# sanfrancisco_barometer_rev_C.net
KiCad netlist of a schematic drawn in EAGLE
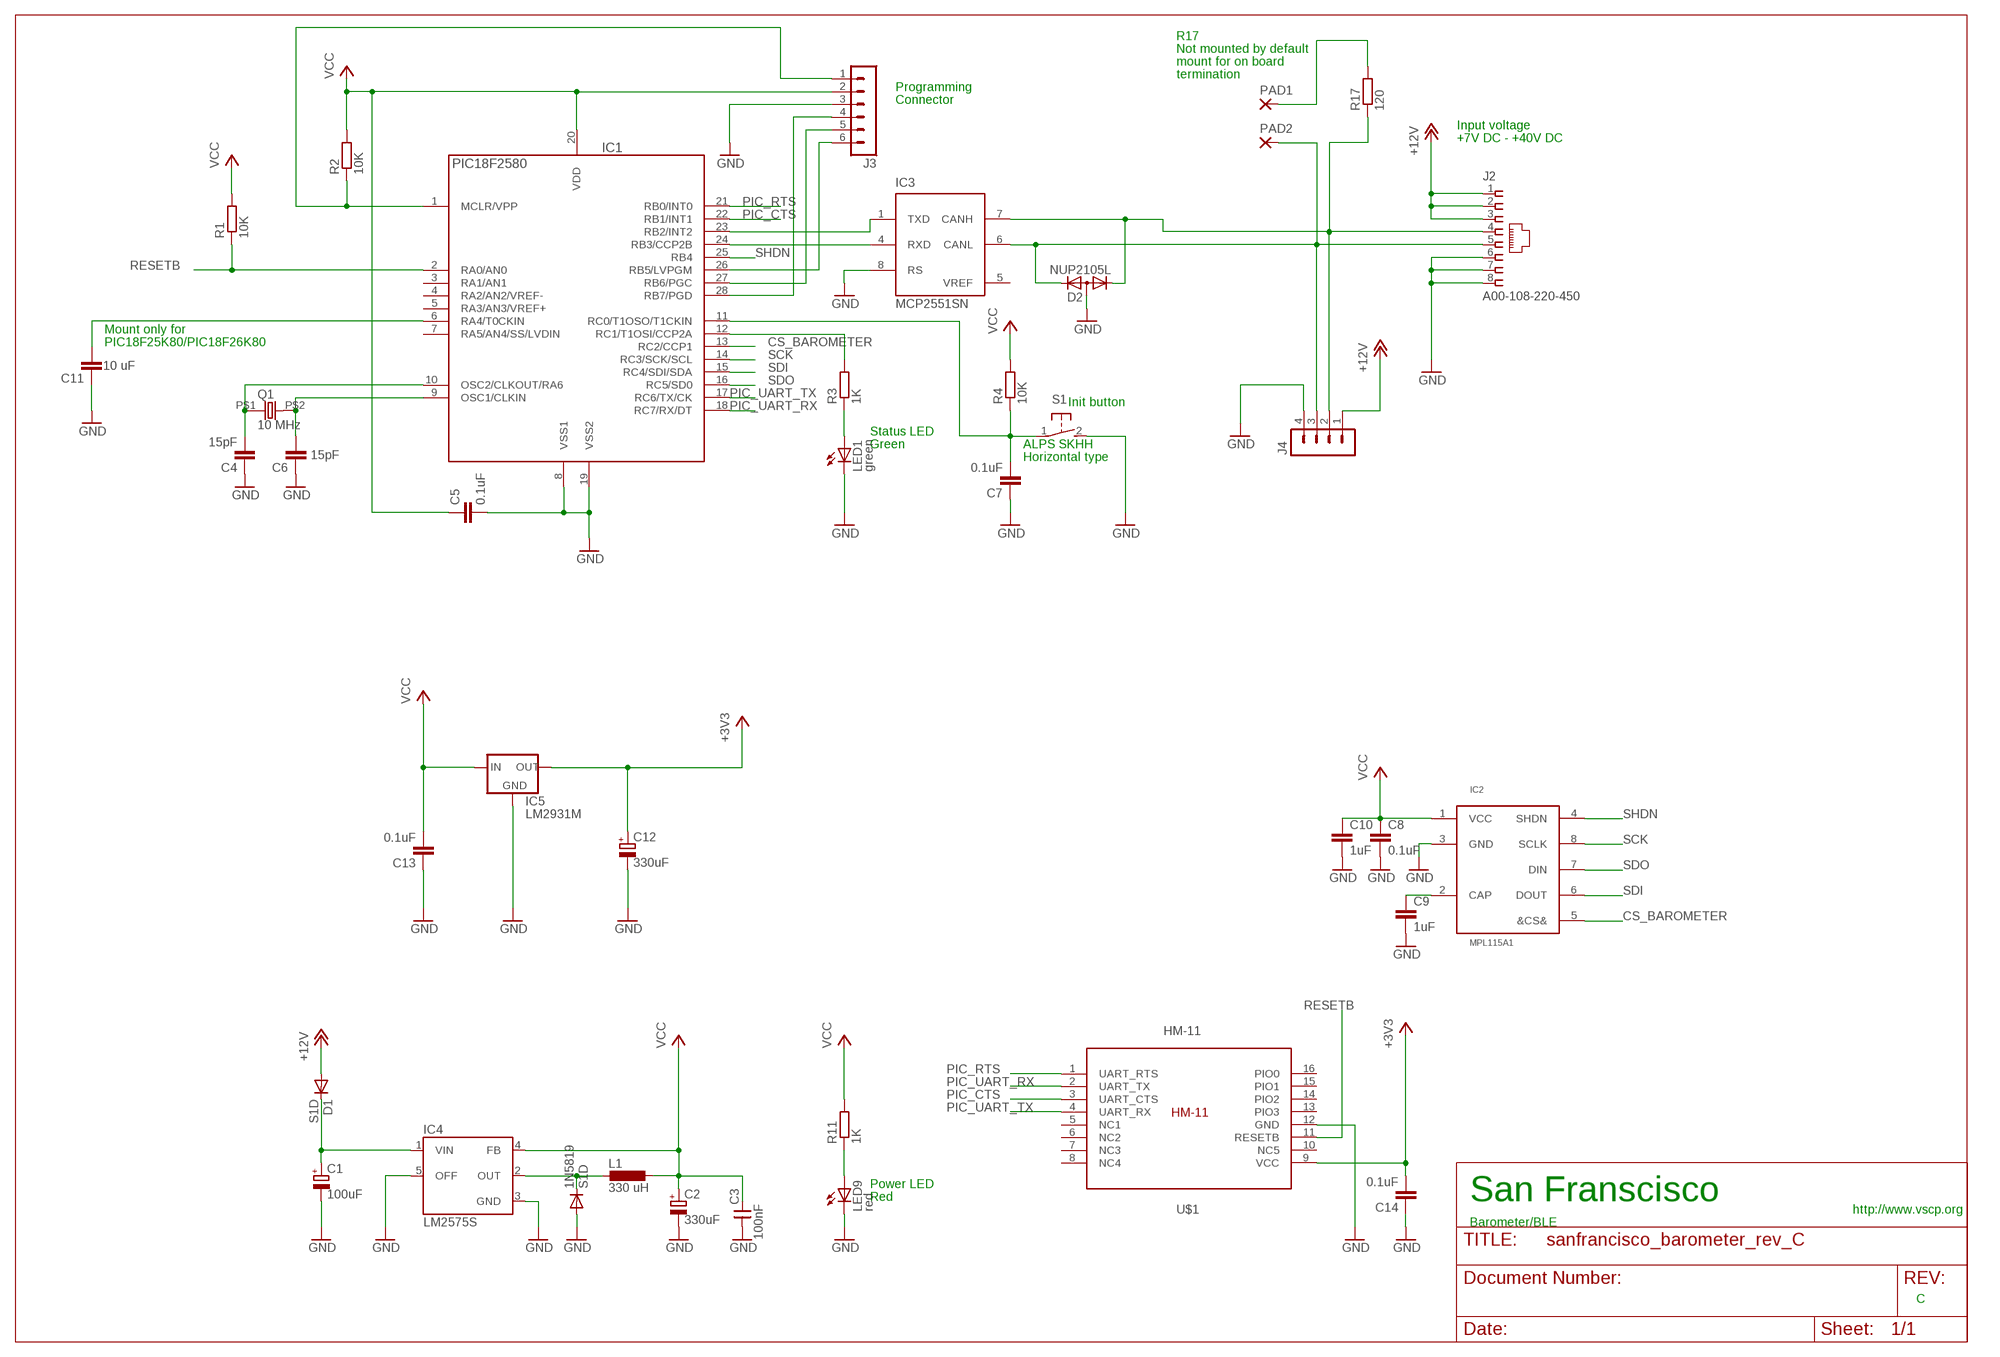
[diagram p0: schematic, sheet 1]

(export (version "E")
  (design (tool "Eeschema 10.0.6"))
  (components
    (comp (ref "1N5819")
      (value "S1D")
      (footprint "eagle-import:SOD123")
      (libsource (lib "eagle-import") (part "DIODE-SOD123"))
    )
    (comp (ref "C1")
      (value "100uF")
      (footprint "eagle-import:PANASONIC_D")
      (libsource (lib "eagle-import") (part "CPOL-EUD"))
    )
    (comp (ref "C2")
      (value "330uF")
      (footprint "eagle-import:PANASONIC_D")
      (libsource (lib "eagle-import") (part "CPOL-EUD"))
    )
    (comp (ref "C3")
      (value "100nF")
      (footprint "eagle-import:0805")
      (libsource (lib "eagle-import") (part "CNP-0805"))
    )
    (comp (ref "C4")
      (value "15pF")
      (footprint "eagle-import:C0805")
      (libsource (lib "eagle-import") (part "C-EUC0805"))
    )
    (comp (ref "C5")
      (value "0.1uF")
      (footprint "eagle-import:C0805")
      (libsource (lib "eagle-import") (part "C-EUC0805"))
    )
    (comp (ref "C6")
      (value "15pF")
      (footprint "eagle-import:C0805")
      (libsource (lib "eagle-import") (part "C-EUC0805"))
    )
    (comp (ref "C7")
      (value "0.1uF")
      (footprint "eagle-import:C0805")
      (libsource (lib "eagle-import") (part "C-EUC0805"))
    )
    (comp (ref "C8")
      (value "0.1uF")
      (footprint "eagle-import:C0805")
      (libsource (lib "eagle-import") (part "C-EUC0805"))
    )
    (comp (ref "C9")
      (value "1uF")
      (footprint "eagle-import:C0805")
      (libsource (lib "eagle-import") (part "C-EUC0805"))
    )
    (comp (ref "C10")
      (value "1uF")
      (footprint "eagle-import:C0805")
      (libsource (lib "eagle-import") (part "C-EUC0805"))
    )
    (comp (ref "C11")
      (value "10 uF")
      (footprint "eagle-import:C0805")
      (libsource (lib "eagle-import") (part "C-EUC0805"))
    )
    (comp (ref "C12")
      (value "330uF")
      (footprint "eagle-import:PANASONIC_D")
      (libsource (lib "eagle-import") (part "CPOL-EUD"))
    )
    (comp (ref "C13")
      (value "0.1uF")
      (footprint "eagle-import:C0805")
      (libsource (lib "eagle-import") (part "C-EUC0805"))
    )
    (comp (ref "C14")
      (value "0.1uF")
      (footprint "eagle-import:C0805")
      (libsource (lib "eagle-import") (part "C-EUC0805"))
    )
    (comp (ref "D1")
      (value "S1D")
      (footprint "eagle-import:SOD123")
      (libsource (lib "eagle-import") (part "DIODE-SOD123"))
    )
    (comp (ref "D2")
      (value "NUP2105L")
      (footprint "eagle-import:SOT23")
      (libsource (lib "eagle-import") (part "DIODE-2CA|ACSOT23"))
    )
    (comp (ref "IC1")
      (value "PIC18F2580")
      (footprint "eagle-import:SO28")
      (libsource (lib "eagle-import") (part "PIC18F252-?I/SOL"))
    )
    (comp (ref "IC2")
      (value "MPL115A1")
      (footprint "eagle-import:LGA8")
      (libsource (lib "eagle-import") (part "MPL115A1"))
    )
    (comp (ref "IC3")
      (value "MCP2551SN")
      (footprint "eagle-import:SO-08")
      (libsource (lib "eagle-import") (part "MCP2551SN"))
    )
    (comp (ref "IC4")
      (value "LM2575S")
      (footprint "eagle-import:TO263-5")
      (libsource (lib "eagle-import") (part "LM2575S"))
    )
    (comp (ref "IC5")
      (value "LM2931M")
      (footprint "eagle-import:SO08")
      (libsource (lib "eagle-import") (part "LM2931M"))
    )
    (comp (ref "J2")
      (value "A00-108-220-450")
      (footprint "eagle-import:RJ-45")
      (libsource (lib "eagle-import") (part "A00-108-220-450"))
    )
    (comp (ref "J3")
      (value "MA06-1")
      (footprint "eagle-import:MA06-1")
      (libsource (lib "eagle-import") (part "MA06-1"))
    )
    (comp (ref "J4")
      (value "MA04-1")
      (footprint "eagle-import:MA04-1")
      (libsource (lib "eagle-import") (part "MA04-1"))
    )
    (comp (ref "L1")
      (value "330 uH")
      (footprint "eagle-import:DO3316P")
      (libsource (lib "eagle-import") (part "DO3316P"))
    )
    (comp (ref "LED1")
      (value "green")
      (footprint "eagle-import:CHIP-LED0805")
      (libsource (lib "eagle-import") (part "LEDCHIP-LED0805"))
    )
    (comp (ref "LED9")
      (value "red")
      (footprint "eagle-import:CHIP-LED0805")
      (libsource (lib "eagle-import") (part "LEDCHIP-LED0805"))
    )
    (comp (ref "PAD1")
      (value "1,6/0,8")
      (footprint "eagle-import:1,6_0,8")
      (libsource (lib "eagle-import") (part "1,6/0,8"))
    )
    (comp (ref "PAD2")
      (value "1,6/0,8")
      (footprint "eagle-import:1,6_0,8")
      (libsource (lib "eagle-import") (part "1,6/0,8"))
    )
    (comp (ref "Q1")
      (value "10 MHz")
      (footprint "eagle-import:9C")
      (libsource (lib "eagle-import") (part "HC-49S"))
    )
    (comp (ref "R1")
      (value "10K")
      (footprint "eagle-import:R0805")
      (libsource (lib "eagle-import") (part "R-EU_R0805"))
    )
    (comp (ref "R2")
      (value "10K")
      (footprint "eagle-import:R0805")
      (libsource (lib "eagle-import") (part "R-EU_R0805"))
    )
    (comp (ref "R3")
      (value "1K")
      (footprint "eagle-import:R0805")
      (libsource (lib "eagle-import") (part "R-EU_R0805"))
    )
    (comp (ref "R4")
      (value "10K")
      (footprint "eagle-import:R0805")
      (libsource (lib "eagle-import") (part "R-EU_R0805"))
    )
    (comp (ref "R11")
      (value "1K")
      (footprint "eagle-import:R0805")
      (libsource (lib "eagle-import") (part "R-EU_R0805"))
    )
    (comp (ref "R17")
      (value "120")
      (footprint "eagle-import:R0805")
      (libsource (lib "eagle-import") (part "R-EU_R0805"))
    )
    (comp (ref "S1")
      (value "31-XX")
      (footprint "eagle-import:B3F-31XX")
      (fields (field (name "MPN") "B3F-3100"))
      (libsource (lib "eagle-import") (part "31-XX"))
    )
    (comp (ref "U$1")
      (value "HM-11")
      (footprint "eagle-import:HM-11")
      (libsource (lib "eagle-import") (part "HM-11"))
    )
  )
  (nets
    (net (code "1") (name "+3V3") (class "Default")
      (node (ref "C12") (pin "+") (pinfunction "+_+") (pintype "passive"))
      (node (ref "C14") (pin "2") (pinfunction "2_2") (pintype "passive"))
      (node (ref "IC5") (pin "1") (pinfunction "OUT_1") (pintype "passive"))
      (node (ref "U$1") (pin "9") (pinfunction "VCC_9") (pintype "power_in"))
    )
    (net (code "2") (name "+12V") (class "Default")
      (node (ref "D1") (pin "A") (pinfunction "A_A") (pintype "passive"))
      (node (ref "J2") (pin "1") (pinfunction "1_1") (pintype "passive"))
      (node (ref "J2") (pin "2") (pinfunction "2_2") (pintype "passive"))
      (node (ref "J2") (pin "3") (pinfunction "3_3") (pintype "passive"))
      (node (ref "J4") (pin "1") (pinfunction "1_1") (pintype "passive"))
    )
    (net (code "3") (name "/CS_BAROMETER") (class "Default")
      (node (ref "IC1") (pin "13") (pinfunction "RC2/CCP1_13") (pintype "bidirectional"))
      (node (ref "IC2") (pin "5") (pinfunction "&CS&_5") (pintype "input"))
    )
    (net (code "4") (name "/PIC_CTS") (class "Default")
      (node (ref "IC1") (pin "22") (pinfunction "RB1/INT1_22") (pintype "bidirectional"))
      (node (ref "U$1") (pin "3") (pinfunction "UART_CTS_3") (pintype "bidirectional"))
    )
    (net (code "5") (name "/PIC_RTS") (class "Default")
      (node (ref "IC1") (pin "21") (pinfunction "RB0/INT0_21") (pintype "bidirectional"))
      (node (ref "U$1") (pin "1") (pinfunction "UART_RTS_1") (pintype "bidirectional"))
    )
    (net (code "6") (name "/PIC_UART_RX") (class "Default")
      (node (ref "IC1") (pin "18") (pinfunction "RC7/RX/DT_18") (pintype "bidirectional"))
      (node (ref "U$1") (pin "2") (pinfunction "UART_TX_2") (pintype "bidirectional"))
    )
    (net (code "7") (name "/PIC_UART_TX") (class "Default")
      (node (ref "IC1") (pin "17") (pinfunction "RC6/TX/CK_17") (pintype "bidirectional"))
      (node (ref "U$1") (pin "4") (pinfunction "UART_RX_4") (pintype "bidirectional"))
    )
    (net (code "8") (name "/RESETB") (class "Default")
      (node (ref "IC1") (pin "2") (pinfunction "RA0/AN0_2") (pintype "bidirectional"))
      (node (ref "R1") (pin "1") (pinfunction "1_1") (pintype "passive"))
      (node (ref "U$1") (pin "11") (pinfunction "RESETB_11") (pintype "bidirectional"))
    )
    (net (code "9") (name "/SCK") (class "Default")
      (node (ref "IC1") (pin "14") (pinfunction "RC3/SCK/SCL_14") (pintype "bidirectional"))
      (node (ref "IC2") (pin "8") (pinfunction "SCLK_8") (pintype "input"))
    )
    (net (code "10") (name "/SDI") (class "Default")
      (node (ref "IC1") (pin "15") (pinfunction "RC4/SDI/SDA_15") (pintype "bidirectional"))
      (node (ref "IC2") (pin "6") (pinfunction "DOUT_6") (pintype "output"))
    )
    (net (code "11") (name "/SDO") (class "Default")
      (node (ref "IC1") (pin "16") (pinfunction "RC5/SD0_16") (pintype "bidirectional"))
      (node (ref "IC2") (pin "7") (pinfunction "DIN_7") (pintype "input"))
    )
    (net (code "12") (name "/SHDN") (class "Default")
      (node (ref "IC1") (pin "25") (pinfunction "RB4_25") (pintype "bidirectional"))
      (node (ref "IC2") (pin "4") (pinfunction "SHDN_4") (pintype "input"))
    )
    (net (code "13") (name "/VREF") (class "Default")
      (node (ref "IC3") (pin "5") (pinfunction "VREF_5") (pintype "power_in"))
    )
    (net (code "14") (name "GND") (class "Default")
      (node (ref "1N5819") (pin "A") (pinfunction "A_A") (pintype "passive"))
      (node (ref "C1") (pin "-") (pinfunction "-_-") (pintype "passive"))
      (node (ref "C10") (pin "2") (pinfunction "2_2") (pintype "passive"))
      (node (ref "C11") (pin "1") (pinfunction "1_1") (pintype "passive"))
      (node (ref "C12") (pin "-") (pinfunction "-_-") (pintype "passive"))
      (node (ref "C13") (pin "1") (pinfunction "1_1") (pintype "passive"))
      (node (ref "C14") (pin "1") (pinfunction "1_1") (pintype "passive"))
      (node (ref "C2") (pin "-") (pinfunction "-_-") (pintype "passive"))
      (node (ref "C3") (pin "1") (pinfunction "1_1") (pintype "passive"))
      (node (ref "C4") (pin "1") (pinfunction "1_1") (pintype "passive"))
      (node (ref "C5") (pin "2") (pinfunction "2_2") (pintype "passive"))
      (node (ref "C6") (pin "1") (pinfunction "1_1") (pintype "passive"))
      (node (ref "C7") (pin "1") (pinfunction "1_1") (pintype "passive"))
      (node (ref "C8") (pin "2") (pinfunction "2_2") (pintype "passive"))
      (node (ref "C9") (pin "2") (pinfunction "2_2") (pintype "passive"))
      (node (ref "D2") (pin "3") (pinfunction "A_3") (pintype "passive"))
      (node (ref "IC1") (pin "19") (pinfunction "VSS2_19") (pintype "power_in"))
      (node (ref "IC1") (pin "8") (pinfunction "VSS1_8") (pintype "power_in"))
      (node (ref "IC2") (pin "3") (pinfunction "GND_3") (pintype "power_in"))
      (node (ref "IC3") (pin "8") (pinfunction "RS_8") (pintype "input"))
      (node (ref "IC4") (pin "3") (pinfunction "GND_3") (pintype "power_in"))
      (node (ref "IC4") (pin "5") (pinfunction "OFF_5") (pintype "input"))
      (node (ref "IC5") (pin "2") (pinfunction "GND_2") (pintype "input"))
      (node (ref "J2") (pin "6") (pinfunction "6_6") (pintype "passive"))
      (node (ref "J2") (pin "7") (pinfunction "7_7") (pintype "passive"))
      (node (ref "J2") (pin "8") (pinfunction "8_8") (pintype "passive"))
      (node (ref "J3") (pin "3") (pinfunction "3_3") (pintype "passive"))
      (node (ref "J4") (pin "4") (pinfunction "4_4") (pintype "passive"))
      (node (ref "LED1") (pin "C") (pinfunction "C_C") (pintype "passive"))
      (node (ref "LED9") (pin "C") (pinfunction "C_C") (pintype "passive"))
      (node (ref "S1") (pin "2") (pinfunction "S_2") (pintype "passive"))
      (node (ref "U$1") (pin "12") (pinfunction "GND_12") (pintype "power_in"))
    )
    (net (code "15") (name "Net-(D2-K1)") (class "Default")
      (node (ref "D2") (pin "1") (pinfunction "K1_1") (pintype "passive"))
      (node (ref "IC3") (pin "7") (pinfunction "CANH_7") (pintype "bidirectional"))
      (node (ref "J2") (pin "4") (pinfunction "4_4") (pintype "passive"))
      (node (ref "J4") (pin "2") (pinfunction "2_2") (pintype "passive"))
      (node (ref "R17") (pin "1") (pinfunction "1_1") (pintype "passive"))
    )
    (net (code "16") (name "Net-(D2-K2)") (class "Default")
      (node (ref "D2") (pin "2") (pinfunction "K2_2") (pintype "passive"))
      (node (ref "IC3") (pin "6") (pinfunction "CANL_6") (pintype "bidirectional"))
      (node (ref "J2") (pin "5") (pinfunction "5_5") (pintype "passive"))
      (node (ref "J4") (pin "3") (pinfunction "3_3") (pintype "passive"))
      (node (ref "PAD2") (pin "1") (pinfunction "P_1") (pintype "passive"))
    )
    (net (code "17") (name "Net-(IC1-MCLR{slash}VPP)") (class "Default")
      (node (ref "IC1") (pin "1") (pinfunction "MCLR/VPP_1") (pintype "input"))
      (node (ref "J3") (pin "1") (pinfunction "1_1") (pintype "passive"))
      (node (ref "R2") (pin "1") (pinfunction "1_1") (pintype "passive"))
    )
    (net (code "18") (name "Net-(IC1-OSC1{slash}CLKIN)") (class "Default")
      (node (ref "C6") (pin "2") (pinfunction "2_2") (pintype "passive"))
      (node (ref "IC1") (pin "9") (pinfunction "OSC1/CLKIN_9") (pintype "input"))
      (node (ref "Q1") (pin "P$2") (pinfunction "2_P$2") (pintype "passive"))
    )
    (net (code "19") (name "Net-(IC1-OSC2{slash}CLKOUT{slash}RA6)") (class "Default")
      (node (ref "C4") (pin "2") (pinfunction "2_2") (pintype "passive"))
      (node (ref "IC1") (pin "10") (pinfunction "OSC2/CLKOUT/RA6_10") (pintype "output"))
      (node (ref "Q1") (pin "P$1") (pinfunction "1_P$1") (pintype "passive"))
    )
    (net (code "20") (name "Net-(IC1-RA4{slash}T0CKIN)") (class "Default")
      (node (ref "C11") (pin "2") (pinfunction "2_2") (pintype "passive"))
      (node (ref "IC1") (pin "6") (pinfunction "RA4/T0CKIN_6") (pintype "open_collector"))
    )
    (net (code "21") (name "Net-(IC1-RB2{slash}INT2)") (class "Default")
      (node (ref "IC1") (pin "23") (pinfunction "RB2/INT2_23") (pintype "bidirectional"))
      (node (ref "IC3") (pin "1") (pinfunction "TXD_1") (pintype "input"))
    )
    (net (code "22") (name "Net-(IC1-RB3{slash}CCP2B)") (class "Default")
      (node (ref "IC1") (pin "24") (pinfunction "RB3/CCP2B_24") (pintype "bidirectional"))
      (node (ref "IC3") (pin "4") (pinfunction "RXD_4") (pintype "output"))
    )
    (net (code "23") (name "Net-(IC1-RB5{slash}LVPGM)") (class "Default")
      (node (ref "IC1") (pin "26") (pinfunction "RB5/LVPGM_26") (pintype "bidirectional"))
      (node (ref "J3") (pin "6") (pinfunction "6_6") (pintype "passive"))
    )
    (net (code "24") (name "Net-(IC1-RB6{slash}PGC)") (class "Default")
      (node (ref "IC1") (pin "27") (pinfunction "RB6/PGC_27") (pintype "bidirectional"))
      (node (ref "J3") (pin "5") (pinfunction "5_5") (pintype "passive"))
    )
    (net (code "25") (name "Net-(IC1-RB7{slash}PGD)") (class "Default")
      (node (ref "IC1") (pin "28") (pinfunction "RB7/PGD_28") (pintype "bidirectional"))
      (node (ref "J3") (pin "4") (pinfunction "4_4") (pintype "passive"))
    )
    (net (code "26") (name "Net-(IC1-RC0{slash}T1OSO{slash}T1CKIN)") (class "Default")
      (node (ref "C7") (pin "2") (pinfunction "2_2") (pintype "passive"))
      (node (ref "IC1") (pin "11") (pinfunction "RC0/T1OSO/T1CKIN_11") (pintype "bidirectional"))
      (node (ref "R4") (pin "1") (pinfunction "1_1") (pintype "passive"))
      (node (ref "S1") (pin "1") (pinfunction "P_1") (pintype "passive"))
    )
    (net (code "27") (name "Net-(IC1-RC1{slash}T1OSI{slash}CCP2A)") (class "Default")
      (node (ref "IC1") (pin "12") (pinfunction "RC1/T1OSI/CCP2A_12") (pintype "bidirectional"))
      (node (ref "R3") (pin "2") (pinfunction "2_2") (pintype "passive"))
    )
    (net (code "28") (name "Net-(IC2-CAP)") (class "Default")
      (node (ref "C9") (pin "1") (pinfunction "1_1") (pintype "passive"))
      (node (ref "IC2") (pin "2") (pinfunction "CAP_2") (pintype "power_in"))
    )
    (net (code "29") (name "Net-(IC4-OUT)") (class "Default")
      (node (ref "1N5819") (pin "C") (pinfunction "C_C") (pintype "passive"))
      (node (ref "IC4") (pin "2") (pinfunction "OUT_2") (pintype "output"))
      (node (ref "L1") (pin "1") (pinfunction "1_1") (pintype "passive"))
    )
    (net (code "30") (name "Net-(IC4-VIN)") (class "Default")
      (node (ref "C1") (pin "+") (pinfunction "+_+") (pintype "passive"))
      (node (ref "D1") (pin "C") (pinfunction "C_C") (pintype "passive"))
      (node (ref "IC4") (pin "1") (pinfunction "VIN_1") (pintype "power_in"))
    )
    (net (code "31") (name "Net-(LED1-PadA)") (class "Default")
      (node (ref "LED1") (pin "A") (pinfunction "A_A") (pintype "passive"))
      (node (ref "R3") (pin "1") (pinfunction "1_1") (pintype "passive"))
    )
    (net (code "32") (name "Net-(LED9-PadA)") (class "Default")
      (node (ref "LED9") (pin "A") (pinfunction "A_A") (pintype "passive"))
      (node (ref "R11") (pin "1") (pinfunction "1_1") (pintype "passive"))
    )
    (net (code "33") (name "Net-(PAD1-P)") (class "Default")
      (node (ref "PAD1") (pin "1") (pinfunction "P_1") (pintype "passive"))
      (node (ref "R17") (pin "2") (pinfunction "2_2") (pintype "passive"))
    )
    (net (code "34") (name "VCC") (class "Default")
      (node (ref "C10") (pin "1") (pinfunction "1_1") (pintype "passive"))
      (node (ref "C13") (pin "2") (pinfunction "2_2") (pintype "passive"))
      (node (ref "C2") (pin "+") (pinfunction "+_+") (pintype "passive"))
      (node (ref "C3") (pin "2") (pinfunction "2_2") (pintype "passive"))
      (node (ref "C5") (pin "1") (pinfunction "1_1") (pintype "passive"))
      (node (ref "C8") (pin "1") (pinfunction "1_1") (pintype "passive"))
      (node (ref "IC1") (pin "20") (pinfunction "VDD_20") (pintype "power_in"))
      (node (ref "IC2") (pin "1") (pinfunction "VCC_1") (pintype "power_in"))
      (node (ref "IC4") (pin "4") (pinfunction "FB_4") (pintype "input"))
      (node (ref "IC5") (pin "8") (pinfunction "IN_8") (pintype "input"))
      (node (ref "J3") (pin "2") (pinfunction "2_2") (pintype "passive"))
      (node (ref "L1") (pin "2") (pinfunction "2_2") (pintype "passive"))
      (node (ref "R1") (pin "2") (pinfunction "2_2") (pintype "passive"))
      (node (ref "R11") (pin "2") (pinfunction "2_2") (pintype "passive"))
      (node (ref "R2") (pin "2") (pinfunction "2_2") (pintype "passive"))
      (node (ref "R4") (pin "2") (pinfunction "2_2") (pintype "passive"))
    )
    (net (code "35") (name "unconnected-(IC1-RA1{slash}AN1-Pad3)") (class "Default")
      (node (ref "IC1") (pin "3") (pinfunction "RA1/AN1_3") (pintype "bidirectional"))
    )
    (net (code "36") (name "unconnected-(IC1-RA2{slash}AN2{slash}VREF--Pad4)") (class "Default")
      (node (ref "IC1") (pin "4") (pinfunction "RA2/AN2/VREF-_4") (pintype "bidirectional"))
    )
    (net (code "37") (name "unconnected-(IC1-RA3{slash}AN3{slash}VREF+-Pad5)") (class "Default")
      (node (ref "IC1") (pin "5") (pinfunction "RA3/AN3/VREF+_5") (pintype "bidirectional"))
    )
    (net (code "38") (name "unconnected-(IC1-RA5{slash}AN4{slash}SS{slash}LVDIN-Pad7)") (class "Default")
      (node (ref "IC1") (pin "7") (pinfunction "RA5/AN4/SS/LVDIN_7") (pintype "bidirectional"))
    )
    (net (code "39") (name "unconnected-(U$1-NC1-Pad5)") (class "Default")
      (node (ref "U$1") (pin "5") (pinfunction "NC1_5") (pintype "no_connect"))
    )
    (net (code "40") (name "unconnected-(U$1-NC2-Pad6)") (class "Default")
      (node (ref "U$1") (pin "6") (pinfunction "NC2_6") (pintype "no_connect"))
    )
    (net (code "41") (name "unconnected-(U$1-NC3-Pad7)") (class "Default")
      (node (ref "U$1") (pin "7") (pinfunction "NC3_7") (pintype "no_connect"))
    )
    (net (code "42") (name "unconnected-(U$1-NC4-Pad8)") (class "Default")
      (node (ref "U$1") (pin "8") (pinfunction "NC4_8") (pintype "no_connect"))
    )
    (net (code "43") (name "unconnected-(U$1-NC5-Pad10)") (class "Default")
      (node (ref "U$1") (pin "10") (pinfunction "NC5_10") (pintype "bidirectional"))
    )
    (net (code "44") (name "unconnected-(U$1-PIO0-Pad16)") (class "Default")
      (node (ref "U$1") (pin "16") (pinfunction "PIO0_16") (pintype "bidirectional"))
    )
    (net (code "45") (name "unconnected-(U$1-PIO1-Pad15)") (class "Default")
      (node (ref "U$1") (pin "15") (pinfunction "PIO1_15") (pintype "bidirectional"))
    )
    (net (code "46") (name "unconnected-(U$1-PIO2-Pad14)") (class "Default")
      (node (ref "U$1") (pin "14") (pinfunction "PIO2_14") (pintype "bidirectional"))
    )
    (net (code "47") (name "unconnected-(U$1-PIO3-Pad13)") (class "Default")
      (node (ref "U$1") (pin "13") (pinfunction "PIO3_13") (pintype "bidirectional"))
    )
  )
)
